# LTE_GPS.net
KiCad netlist of a schematic drawn in Altium Designer
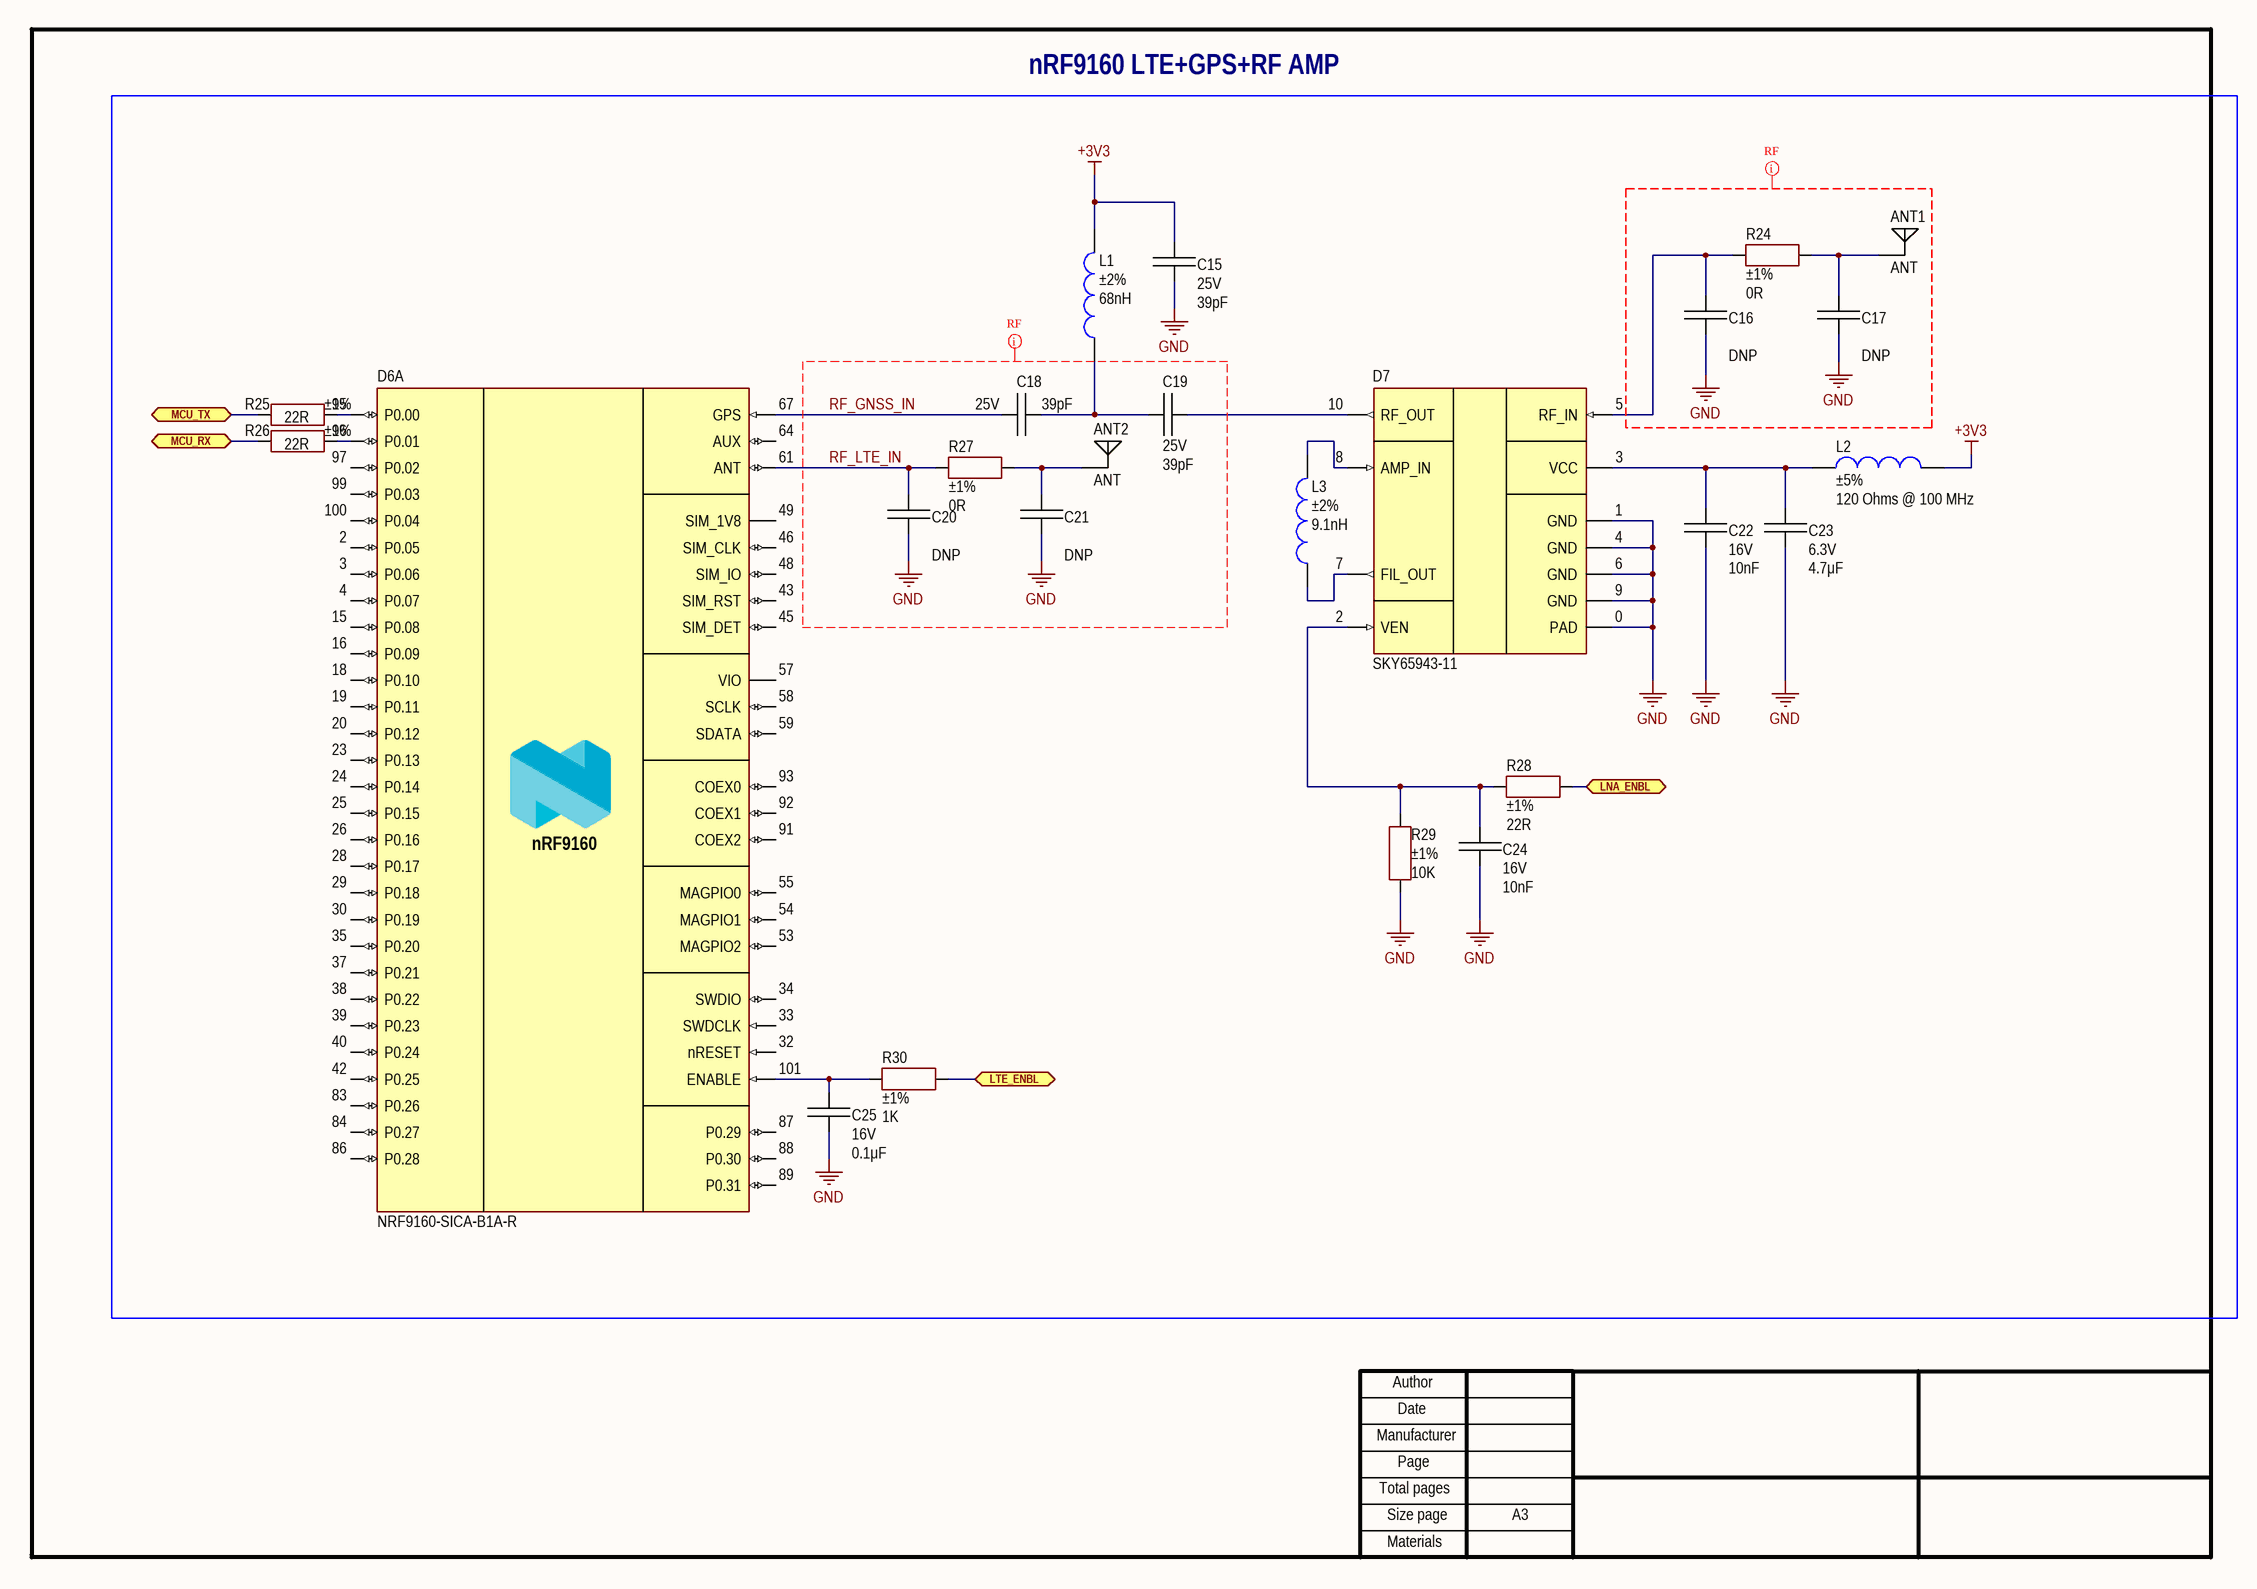
[diagram p0: LTE+GPS.SchDoc]

(export (version "E")
  (design (tool "Eeschema 10.0.6"))
  (components
    (comp (ref "ANT1")
      (value "~")
      (footprint "ANT: ANT2012LL00R2400A")
      (description "2.45GHz Bluetooth, ISM, Wi-Fi, Zigbee Chip RF Antenna 2.4GHz ~ 2.5GHz 3.77dBi Solder Surface Mount")
      (fields
        (field (name "MANUFACTURER") "Yageo")
        (field (name "VALUEMANUFACTURERPARTNUMBER") "Ceramic antenna, 2x1.25mm")
        (field (name "COMMENTTEXT") "ANT")
      )
      (libsource (lib "MyLib") (part "ANT2012LL00R2400A"))
    )
    (comp (ref "ANT2")
      (value "~")
      (footprint "ANT: ANT2012LL00R2400A")
      (description "2.45GHz Bluetooth, ISM, Wi-Fi, Zigbee Chip RF Antenna 2.4GHz ~ 2.5GHz 3.77dBi Solder Surface Mount")
      (fields
        (field (name "MANUFACTURER") "Yageo")
        (field (name "VALUEMANUFACTURERPARTNUMBER") "Ceramic antenna, 2x1.25mm")
        (field (name "COMMENTTEXT") "ANT")
      )
      (libsource (lib "MyLib") (part "ANT2012LL00R2400A"))
    )
    (comp (ref "C15")
      (value "39pF")
      (footprint "CAP: 0201")
      (description "39 pF ±5% 25V Ceramic Capacitor C0G, NP0 0201 (0603 Metric)")
      (fields
        (field (name "MANUFACTURER") "Murata Electronics")
        (field (name "PARTNUMBER") "GRM0335C1E390JA01D")
        (field (name "VOLTAGE") "25V")
      )
      (libsource (lib "capacitor") (part "Ceramic_0201"))
    )
    (comp (ref "C16")
      (value "DNP")
      (footprint "CAP: 0201")
      (fields (field (name "VALUEMANUFACTURERPARTNUMBER") "Ceramic capacitor, DNP, , , , 0201, -55...+125°C"))
      (libsource (lib "capacitor") (part "Ceramic_0201"))
    )
    (comp (ref "C17")
      (value "DNP")
      (footprint "CAP: 0201")
      (fields (field (name "VALUEMANUFACTURERPARTNUMBER") "Ceramic capacitor, DNP, , , , 0201, -55...+125°C"))
      (libsource (lib "capacitor") (part "Ceramic_0201"))
    )
    (comp (ref "C18")
      (value "39pF")
      (footprint "CAP: 0201")
      (description "39 pF ±5% 25V Ceramic Capacitor C0G, NP0 0201 (0603 Metric)")
      (fields
        (field (name "MANUFACTURER") "Murata Electronics")
        (field (name "PARTNUMBER") "GRM0335C1E390JA01D")
        (field (name "VOLTAGE") "25V")
      )
      (libsource (lib "capacitor") (part "Ceramic_0201"))
    )
    (comp (ref "C19")
      (value "39pF")
      (footprint "CAP: 0201")
      (description "39 pF ±5% 25V Ceramic Capacitor C0G, NP0 0201 (0603 Metric)")
      (fields
        (field (name "MANUFACTURER") "Murata Electronics")
        (field (name "PARTNUMBER") "GRM0335C1E390JA01D")
        (field (name "VOLTAGE") "25V")
      )
      (libsource (lib "capacitor") (part "Ceramic_0201"))
    )
    (comp (ref "C20")
      (value "DNP")
      (footprint "CAP: 0201")
      (fields (field (name "VALUEMANUFACTURERPARTNUMBER") "Ceramic capacitor, DNP, , , , 0201, -55...+125°C"))
      (libsource (lib "capacitor") (part "Ceramic_0201"))
    )
    (comp (ref "C21")
      (value "DNP")
      (footprint "CAP: 0201")
      (fields (field (name "VALUEMANUFACTURERPARTNUMBER") "Ceramic capacitor, DNP, , , , 0201, -55...+125°C"))
      (libsource (lib "capacitor") (part "Ceramic_0201"))
    )
    (comp (ref "C22")
      (value "10nF")
      (footprint "CAP: 0201")
      (description "10000 pF ±10% 16V Ceramic Capacitor X7R 0201 (0603 Metric)")
      (fields
        (field (name "MANUFACTURER") "Yageo")
        (field (name "PARTNUMBER") "CC0201KRX7R7BB103")
        (field (name "VOLTAGE") "16V")
      )
      (libsource (lib "capacitor") (part "Ceramic_0201"))
    )
    (comp (ref "C23")
      (value "4.7μF")
      (footprint "CAP: 0603_NO_SILK")
      (description "4.7 µF ±20% 6.3V Ceramic Capacitor X7R 0603 (1608 Metric)")
      (fields
        (field (name "MANUFACTURER") "Yageo")
        (field (name "PARTNUMBER") "CC0603MRX7R5BB475")
        (field (name "VOLTAGE") "6.3V")
      )
      (libsource (lib "capacitor") (part "Ceramic_0603"))
    )
    (comp (ref "C24")
      (value "10nF")
      (footprint "CAP: 0201")
      (description "10000 pF ±10% 16V Ceramic Capacitor X7R 0201 (0603 Metric)")
      (fields
        (field (name "MANUFACTURER") "Yageo")
        (field (name "PARTNUMBER") "CC0201KRX7R7BB103")
        (field (name "VOLTAGE") "16V")
      )
      (libsource (lib "capacitor") (part "Ceramic_0201"))
    )
    (comp (ref "C25")
      (value "0.1μF")
      (footprint "CAP: 0402_NO_SILK")
      (description "0.1 µF ±10% 16V Ceramic Capacitor X7R 0402 (1005 Metric)")
      (fields
        (field (name "MANUFACTURER") "Yageo")
        (field (name "PARTNUMBER") "CC0402KRX7R7BB104")
        (field (name "VOLTAGE") "16V")
      )
      (libsource (lib "capacitor") (part "Ceramic_0402"))
    )
    (comp (ref "D6")
      (value "~")
      (footprint "MOD: NRF9160")
      (description "LTE/GSM module")
      (fields
        (field (name "MANUFACTURER") "Nordic Semiconductor")
        (field (name "VALUEMANUFACTURERPARTNUMBER") "LTE/GSM module, LTE-M/NB-IoT/GPS, 2.4GHz, , , , , 3...5.5V, -40...+85°C, 127-LGA")
        (field (name "PARTNUMBER") "NRF9160-SICA-B1A-R")
      )
      (libsource (lib "MyLib") (part "nRF9160"))
    )
    (comp (ref "D7")
      (value "~")
      (footprint "IC: SKY65943-11")
      (description "RF front-end")
      (fields
        (field (name "MANUFACTURER") "Skyworks Solutions")
        (field (name "VALUEMANUFACTURERPARTNUMBER") "IC RF amplifier, 2.7 GHz, 19dB, -40...+125°C, 10-SMD Module")
        (field (name "PARTNUMBER") "SKY65943-11")
      )
      (libsource (lib "MyLib") (part "SKY65943-11"))
    )
    (comp (ref "L1")
      (value "68nH")
      (footprint "IND: 0402")
      (description "68 nH Unshielded Wirewound Inductor 320 mA 1.1Ohm Max 0402 (1005 Metric)")
      (fields
        (field (name "MANUFACTURER") "Murata Electronics")
        (field (name "PARTNUMBER") "LQW15AN68NG80D")
        (field (name "TOLERANCE") "±2%")
      )
      (libsource (lib "inductor") (part "Inductor_0402"))
    )
    (comp (ref "L2")
      (value "120 Ohms @ 100 MHz")
      (footprint "IND: 0402")
      (description "120 Ohms @ 100 MHz 1 Power Line Ferrite Bead 0402 (1005 Metric) 2A 55mOhm")
      (fields
        (field (name "MANUFACTURER") "Murata Electronics")
        (field (name "PARTNUMBER") "BLM15PX121SN1D")
        (field (name "TOLERANCE") "±5%")
      )
      (libsource (lib "inductor") (part "Inductor_0402"))
    )
    (comp (ref "L3")
      (value "9.1nH")
      (footprint "IND: 0402")
      (description "9.1 nH Unshielded Wirewound Inductor 1.4 A 80mOhm Max 0402 (1005 Metric)")
      (fields
        (field (name "MANUFACTURER") "Murata Electronics")
        (field (name "PARTNUMBER") "LQW15AN9N1G8ZD")
        (field (name "TOLERANCE") "±2%")
      )
      (libsource (lib "inductor") (part "Inductor_0402"))
    )
    (comp (ref "R24")
      (value "0R")
      (footprint "RES: 0201")
      (description "0 Ohms Jumper 0.05W, 1/20W Chip Resistor 0201 (0603 Metric) Moisture Resistant Thick Film")
      (fields
        (field (name "MANUFACTURER") "Yageo")
        (field (name "PARTNUMBER") "RC0201FR-070RL")
        (field (name "TOLERANCE") "±1%")
      )
      (libsource (lib "") (part "Resistor_0201_2"))
    )
    (comp (ref "R25")
      (value "22R")
      (footprint "RES: 0201")
      (description "22 Ohms ±1% 0.05W, 1/20W Chip Resistor 0201 (0603 Metric) Moisture Resistant Thick Film")
      (fields
        (field (name "MANUFACTURER") "Yageo")
        (field (name "PARTNUMBER") "RC0201FR-0722RL")
        (field (name "TOLERANCE") "±1%")
      )
      (libsource (lib "") (part "Resistor_0201_1"))
    )
    (comp (ref "R26")
      (value "22R")
      (footprint "RES: 0201")
      (description "22 Ohms ±1% 0.05W, 1/20W Chip Resistor 0201 (0603 Metric) Moisture Resistant Thick Film")
      (fields
        (field (name "MANUFACTURER") "Yageo")
        (field (name "PARTNUMBER") "RC0201FR-0722RL")
        (field (name "TOLERANCE") "±1%")
      )
      (libsource (lib "") (part "Resistor_0201_1"))
    )
    (comp (ref "R27")
      (value "0R")
      (footprint "RES: 0201")
      (description "0 Ohms Jumper 0.05W, 1/20W Chip Resistor 0201 (0603 Metric) Moisture Resistant Thick Film")
      (fields
        (field (name "MANUFACTURER") "Yageo")
        (field (name "PARTNUMBER") "RC0201FR-070RL")
        (field (name "TOLERANCE") "±1%")
      )
      (libsource (lib "") (part "Resistor_0201_2"))
    )
    (comp (ref "R28")
      (value "22R")
      (footprint "RES: 0201")
      (description "22 Ohms ±1% 0.05W, 1/20W Chip Resistor 0201 (0603 Metric) Moisture Resistant Thick Film")
      (fields
        (field (name "MANUFACTURER") "Yageo")
        (field (name "PARTNUMBER") "RC0201FR-0722RL")
        (field (name "TOLERANCE") "±1%")
      )
      (libsource (lib "resistor") (part "Resistor_0201"))
    )
    (comp (ref "R29")
      (value "10K")
      (footprint "RES: 0201")
      (description "10 kOhms ±1% 0.05W, 1/20W Chip Resistor 0201 (0603 Metric) Moisture Resistant Thick Film")
      (fields
        (field (name "MANUFACTURER") "Yageo")
        (field (name "PARTNUMBER") "RC0201JR-0710KL")
        (field (name "TOLERANCE") "±1%")
      )
      (libsource (lib "resistor") (part "Resistor_0201"))
    )
    (comp (ref "R30")
      (value "1K")
      (footprint "RES: 0201")
      (description "1 kOhms ±1% 0.05W, 1/20W Chip Resistor 0201 (0603 Metric) Moisture Resistant Thick Film")
      (fields
        (field (name "MANUFACTURER") "Yageo")
        (field (name "PARTNUMBER") "RC0201JR-071KL")
        (field (name "TOLERANCE") "±1%")
      )
      (libsource (lib "") (part "Resistor_0201_1"))
    )
  )
  (nets
    (net (code "1") (name "+3V3") (class "Default")
      (node (ref "C15") (pin "1") (pinfunction "1_1") (pintype "passive"))
      (node (ref "L1") (pin "1") (pinfunction "1_1") (pintype "passive"))
      (node (ref "L2") (pin "1") (pinfunction "1_1") (pintype "passive"))
    )
    (net (code "2") (name "/LNA_ENBL") (class "Default")
      (node (ref "R28") (pin "2") (pinfunction "2_2") (pintype "passive"))
    )
    (net (code "3") (name "/LTE_ENBL") (class "Default")
      (node (ref "R30") (pin "1") (pinfunction "1_1") (pintype "passive"))
    )
    (net (code "4") (name "/MCU_RX") (class "Default")
      (node (ref "R26") (pin "2") (pinfunction "2_2") (pintype "passive"))
    )
    (net (code "5") (name "/MCU_TX") (class "Default")
      (node (ref "R25") (pin "2") (pinfunction "2_2") (pintype "passive"))
    )
    (net (code "6") (name "/RF_GNSS_IN") (class "Default")
      (node (ref "C18") (pin "2") (pinfunction "2_2") (pintype "passive"))
      (node (ref "D6") (pin "67") (pinfunction "GPS_67") (pintype "input"))
    )
    (net (code "7") (name "/RF_LTE_IN") (class "Default")
      (node (ref "C20") (pin "2") (pinfunction "2_2") (pintype "passive"))
      (node (ref "D6") (pin "61") (pinfunction "ANT_61") (pintype "bidirectional"))
      (node (ref "R27") (pin "2") (pinfunction "2_2") (pintype "passive"))
    )
    (net (code "8") (name "GND") (class "Default")
      (node (ref "C15") (pin "2") (pinfunction "2_2") (pintype "passive"))
      (node (ref "C16") (pin "1") (pinfunction "1_1") (pintype "passive"))
      (node (ref "C17") (pin "1") (pinfunction "1_1") (pintype "passive"))
      (node (ref "C20") (pin "1") (pinfunction "1_1") (pintype "passive"))
      (node (ref "C21") (pin "1") (pinfunction "1_1") (pintype "passive"))
      (node (ref "C22") (pin "1") (pinfunction "1_1") (pintype "passive"))
      (node (ref "C23") (pin "1") (pinfunction "1_1") (pintype "passive"))
      (node (ref "C24") (pin "1") (pinfunction "1_1") (pintype "passive"))
      (node (ref "C25") (pin "1") (pinfunction "1_1") (pintype "passive"))
      (node (ref "D7") (pin "0") (pinfunction "PAD_0") (pintype "power_in"))
      (node (ref "D7") (pin "1") (pinfunction "GND_1") (pintype "power_in"))
      (node (ref "D7") (pin "4") (pinfunction "GND_4") (pintype "power_in"))
      (node (ref "D7") (pin "6") (pinfunction "GND_6") (pintype "power_in"))
      (node (ref "D7") (pin "9") (pinfunction "GND_9") (pintype "power_in"))
      (node (ref "R29") (pin "1") (pinfunction "1_1") (pintype "passive"))
    )
    (net (code "9") (name "Net-(ANT1-Pad1)") (class "Default")
      (node (ref "ANT1") (pin "1") (pinfunction "1_1") (pintype "passive"))
      (node (ref "C17") (pin "2") (pinfunction "2_2") (pintype "passive"))
      (node (ref "R24") (pin "1") (pinfunction "1_1") (pintype "passive"))
    )
    (net (code "10") (name "Net-(ANT2-Pad1)") (class "Default")
      (node (ref "ANT2") (pin "1") (pinfunction "1_1") (pintype "passive"))
      (node (ref "C21") (pin "2") (pinfunction "2_2") (pintype "passive"))
      (node (ref "R27") (pin "1") (pinfunction "1_1") (pintype "passive"))
    )
    (net (code "11") (name "Net-(C18-Pad1)") (class "Default")
      (node (ref "C18") (pin "1") (pinfunction "1_1") (pintype "passive"))
      (node (ref "C19") (pin "2") (pinfunction "2_2") (pintype "passive"))
      (node (ref "L1") (pin "2") (pinfunction "2_2") (pintype "passive"))
    )
    (net (code "12") (name "Net-(D6A-ENABLE)") (class "Default")
      (node (ref "C25") (pin "2") (pinfunction "2_2") (pintype "passive"))
      (node (ref "D6") (pin "101") (pinfunction "ENABLE_101") (pintype "input"))
      (node (ref "R30") (pin "2") (pinfunction "2_2") (pintype "passive"))
    )
    (net (code "13") (name "Net-(D6A-P0.00)") (class "Default")
      (node (ref "D6") (pin "95") (pinfunction "P0.00_95") (pintype "bidirectional"))
      (node (ref "R25") (pin "1") (pinfunction "1_1") (pintype "passive"))
    )
    (net (code "14") (name "Net-(D6A-P0.01)") (class "Default")
      (node (ref "D6") (pin "96") (pinfunction "P0.01_96") (pintype "bidirectional"))
      (node (ref "R26") (pin "1") (pinfunction "1_1") (pintype "passive"))
    )
    (net (code "15") (name "Net-(D7-AMP_IN)") (class "Default")
      (node (ref "D7") (pin "8") (pinfunction "AMP_IN_8") (pintype "input"))
      (node (ref "L3") (pin "1") (pinfunction "1_1") (pintype "passive"))
    )
    (net (code "16") (name "Net-(D7-FIL_OUT)") (class "Default")
      (node (ref "D7") (pin "7") (pinfunction "FIL_OUT_7") (pintype "output"))
      (node (ref "L3") (pin "2") (pinfunction "2_2") (pintype "passive"))
    )
    (net (code "17") (name "Net-(D7-RF_IN)") (class "Default")
      (node (ref "C16") (pin "2") (pinfunction "2_2") (pintype "passive"))
      (node (ref "D7") (pin "5") (pinfunction "RF_IN_5") (pintype "input"))
      (node (ref "R24") (pin "2") (pinfunction "2_2") (pintype "passive"))
    )
    (net (code "18") (name "Net-(D7-RF_OUT)") (class "Default")
      (node (ref "C19") (pin "1") (pinfunction "1_1") (pintype "passive"))
      (node (ref "D7") (pin "10") (pinfunction "RF_OUT_10") (pintype "output"))
    )
    (net (code "19") (name "Net-(D7-VCC)") (class "Default")
      (node (ref "C22") (pin "2") (pinfunction "2_2") (pintype "passive"))
      (node (ref "C23") (pin "2") (pinfunction "2_2") (pintype "passive"))
      (node (ref "D7") (pin "3") (pinfunction "VCC_3") (pintype "power_in"))
      (node (ref "L2") (pin "2") (pinfunction "2_2") (pintype "passive"))
    )
    (net (code "20") (name "Net-(D7-VEN)") (class "Default")
      (node (ref "C24") (pin "2") (pinfunction "2_2") (pintype "passive"))
      (node (ref "D7") (pin "2") (pinfunction "VEN_2") (pintype "input"))
      (node (ref "R28") (pin "1") (pinfunction "1_1") (pintype "passive"))
      (node (ref "R29") (pin "2") (pinfunction "2_2") (pintype "passive"))
    )
    (net (code "21") (name "unconnected-(D6A-AUX-Pad64)") (class "Default")
      (node (ref "D6") (pin "64") (pinfunction "AUX_64") (pintype "bidirectional"))
    )
    (net (code "22") (name "unconnected-(D6A-COEX0-Pad93)") (class "Default")
      (node (ref "D6") (pin "93") (pinfunction "COEX0_93") (pintype "bidirectional"))
    )
    (net (code "23") (name "unconnected-(D6A-COEX1-Pad92)") (class "Default")
      (node (ref "D6") (pin "92") (pinfunction "COEX1_92") (pintype "bidirectional"))
    )
    (net (code "24") (name "unconnected-(D6A-COEX2-Pad91)") (class "Default")
      (node (ref "D6") (pin "91") (pinfunction "COEX2_91") (pintype "bidirectional"))
    )
    (net (code "25") (name "unconnected-(D6A-MAGPIO0-Pad55)") (class "Default")
      (node (ref "D6") (pin "55") (pinfunction "MAGPIO0_55") (pintype "bidirectional"))
    )
    (net (code "26") (name "unconnected-(D6A-MAGPIO1-Pad54)") (class "Default")
      (node (ref "D6") (pin "54") (pinfunction "MAGPIO1_54") (pintype "bidirectional"))
    )
    (net (code "27") (name "unconnected-(D6A-MAGPIO2-Pad53)") (class "Default")
      (node (ref "D6") (pin "53") (pinfunction "MAGPIO2_53") (pintype "bidirectional"))
    )
    (net (code "28") (name "unconnected-(D6A-P0.02-Pad97)") (class "Default")
      (node (ref "D6") (pin "97") (pinfunction "P0.02_97") (pintype "bidirectional"))
    )
    (net (code "29") (name "unconnected-(D6A-P0.03-Pad99)") (class "Default")
      (node (ref "D6") (pin "99") (pinfunction "P0.03_99") (pintype "bidirectional"))
    )
    (net (code "30") (name "unconnected-(D6A-P0.04-Pad100)") (class "Default")
      (node (ref "D6") (pin "100") (pinfunction "P0.04_100") (pintype "bidirectional"))
    )
    (net (code "31") (name "unconnected-(D6A-P0.05-Pad2)") (class "Default")
      (node (ref "D6") (pin "2") (pinfunction "P0.05_2") (pintype "bidirectional"))
    )
    (net (code "32") (name "unconnected-(D6A-P0.06-Pad3)") (class "Default")
      (node (ref "D6") (pin "3") (pinfunction "P0.06_3") (pintype "bidirectional"))
    )
    (net (code "33") (name "unconnected-(D6A-P0.07-Pad4)") (class "Default")
      (node (ref "D6") (pin "4") (pinfunction "P0.07_4") (pintype "bidirectional"))
    )
    (net (code "34") (name "unconnected-(D6A-P0.08-Pad15)") (class "Default")
      (node (ref "D6") (pin "15") (pinfunction "P0.08_15") (pintype "bidirectional"))
    )
    (net (code "35") (name "unconnected-(D6A-P0.09-Pad16)") (class "Default")
      (node (ref "D6") (pin "16") (pinfunction "P0.09_16") (pintype "bidirectional"))
    )
    (net (code "36") (name "unconnected-(D6A-P0.10-Pad18)") (class "Default")
      (node (ref "D6") (pin "18") (pinfunction "P0.10_18") (pintype "bidirectional"))
    )
    (net (code "37") (name "unconnected-(D6A-P0.11-Pad19)") (class "Default")
      (node (ref "D6") (pin "19") (pinfunction "P0.11_19") (pintype "bidirectional"))
    )
    (net (code "38") (name "unconnected-(D6A-P0.12-Pad20)") (class "Default")
      (node (ref "D6") (pin "20") (pinfunction "P0.12_20") (pintype "bidirectional"))
    )
    (net (code "39") (name "unconnected-(D6A-P0.13-Pad23)") (class "Default")
      (node (ref "D6") (pin "23") (pinfunction "P0.13_23") (pintype "bidirectional"))
    )
    (net (code "40") (name "unconnected-(D6A-P0.14-Pad24)") (class "Default")
      (node (ref "D6") (pin "24") (pinfunction "P0.14_24") (pintype "bidirectional"))
    )
    (net (code "41") (name "unconnected-(D6A-P0.15-Pad25)") (class "Default")
      (node (ref "D6") (pin "25") (pinfunction "P0.15_25") (pintype "bidirectional"))
    )
    (net (code "42") (name "unconnected-(D6A-P0.16-Pad26)") (class "Default")
      (node (ref "D6") (pin "26") (pinfunction "P0.16_26") (pintype "bidirectional"))
    )
    (net (code "43") (name "unconnected-(D6A-P0.17-Pad28)") (class "Default")
      (node (ref "D6") (pin "28") (pinfunction "P0.17_28") (pintype "bidirectional"))
    )
    (net (code "44") (name "unconnected-(D6A-P0.18-Pad29)") (class "Default")
      (node (ref "D6") (pin "29") (pinfunction "P0.18_29") (pintype "bidirectional"))
    )
    (net (code "45") (name "unconnected-(D6A-P0.19-Pad30)") (class "Default")
      (node (ref "D6") (pin "30") (pinfunction "P0.19_30") (pintype "bidirectional"))
    )
    (net (code "46") (name "unconnected-(D6A-P0.20-Pad35)") (class "Default")
      (node (ref "D6") (pin "35") (pinfunction "P0.20_35") (pintype "bidirectional"))
    )
    (net (code "47") (name "unconnected-(D6A-P0.21-Pad37)") (class "Default")
      (node (ref "D6") (pin "37") (pinfunction "P0.21_37") (pintype "bidirectional"))
    )
    (net (code "48") (name "unconnected-(D6A-P0.22-Pad38)") (class "Default")
      (node (ref "D6") (pin "38") (pinfunction "P0.22_38") (pintype "bidirectional"))
    )
    (net (code "49") (name "unconnected-(D6A-P0.23-Pad39)") (class "Default")
      (node (ref "D6") (pin "39") (pinfunction "P0.23_39") (pintype "bidirectional"))
    )
    (net (code "50") (name "unconnected-(D6A-P0.24-Pad40)") (class "Default")
      (node (ref "D6") (pin "40") (pinfunction "P0.24_40") (pintype "bidirectional"))
    )
    (net (code "51") (name "unconnected-(D6A-P0.25-Pad42)") (class "Default")
      (node (ref "D6") (pin "42") (pinfunction "P0.25_42") (pintype "bidirectional"))
    )
    (net (code "52") (name "unconnected-(D6A-P0.26-Pad83)") (class "Default")
      (node (ref "D6") (pin "83") (pinfunction "P0.26_83") (pintype "bidirectional"))
    )
    (net (code "53") (name "unconnected-(D6A-P0.27-Pad84)") (class "Default")
      (node (ref "D6") (pin "84") (pinfunction "P0.27_84") (pintype "bidirectional"))
    )
    (net (code "54") (name "unconnected-(D6A-P0.28-Pad86)") (class "Default")
      (node (ref "D6") (pin "86") (pinfunction "P0.28_86") (pintype "bidirectional"))
    )
    (net (code "55") (name "unconnected-(D6A-P0.29-Pad87)") (class "Default")
      (node (ref "D6") (pin "87") (pinfunction "P0.29_87") (pintype "bidirectional"))
    )
    (net (code "56") (name "unconnected-(D6A-P0.30-Pad88)") (class "Default")
      (node (ref "D6") (pin "88") (pinfunction "P0.30_88") (pintype "bidirectional"))
    )
    (net (code "57") (name "unconnected-(D6A-P0.31-Pad89)") (class "Default")
      (node (ref "D6") (pin "89") (pinfunction "P0.31_89") (pintype "bidirectional"))
    )
    (net (code "58") (name "unconnected-(D6A-SCLK-Pad58)") (class "Default")
      (node (ref "D6") (pin "58") (pinfunction "SCLK_58") (pintype "bidirectional"))
    )
    (net (code "59") (name "unconnected-(D6A-SDATA-Pad59)") (class "Default")
      (node (ref "D6") (pin "59") (pinfunction "SDATA_59") (pintype "bidirectional"))
    )
    (net (code "60") (name "unconnected-(D6A-SIM_1V8-Pad49)") (class "Default")
      (node (ref "D6") (pin "49") (pinfunction "SIM_1V8_49") (pintype "power_in"))
    )
    (net (code "61") (name "unconnected-(D6A-SIM_CLK-Pad46)") (class "Default")
      (node (ref "D6") (pin "46") (pinfunction "SIM_CLK_46") (pintype "bidirectional"))
    )
    (net (code "62") (name "unconnected-(D6A-SIM_DET-Pad45)") (class "Default")
      (node (ref "D6") (pin "45") (pinfunction "SIM_DET_45") (pintype "bidirectional"))
    )
    (net (code "63") (name "unconnected-(D6A-SIM_IO-Pad48)") (class "Default")
      (node (ref "D6") (pin "48") (pinfunction "SIM_IO_48") (pintype "bidirectional"))
    )
    (net (code "64") (name "unconnected-(D6A-SIM_RST-Pad43)") (class "Default")
      (node (ref "D6") (pin "43") (pinfunction "SIM_RST_43") (pintype "bidirectional"))
    )
    (net (code "65") (name "unconnected-(D6A-SWDCLK-Pad33)") (class "Default")
      (node (ref "D6") (pin "33") (pinfunction "SWDCLK_33") (pintype "input"))
    )
    (net (code "66") (name "unconnected-(D6A-SWDIO-Pad34)") (class "Default")
      (node (ref "D6") (pin "34") (pinfunction "SWDIO_34") (pintype "bidirectional"))
    )
    (net (code "67") (name "unconnected-(D6A-VIO-Pad57)") (class "Default")
      (node (ref "D6") (pin "57") (pinfunction "VIO_57") (pintype "power_in"))
    )
    (net (code "68") (name "unconnected-(D6A-nRESET-Pad32)") (class "Default")
      (node (ref "D6") (pin "32") (pinfunction "nRESET_32") (pintype "input"))
    )
  )
)
